# esp32_devkit.net
KiCad netlist of a schematic drawn in Altium Designer
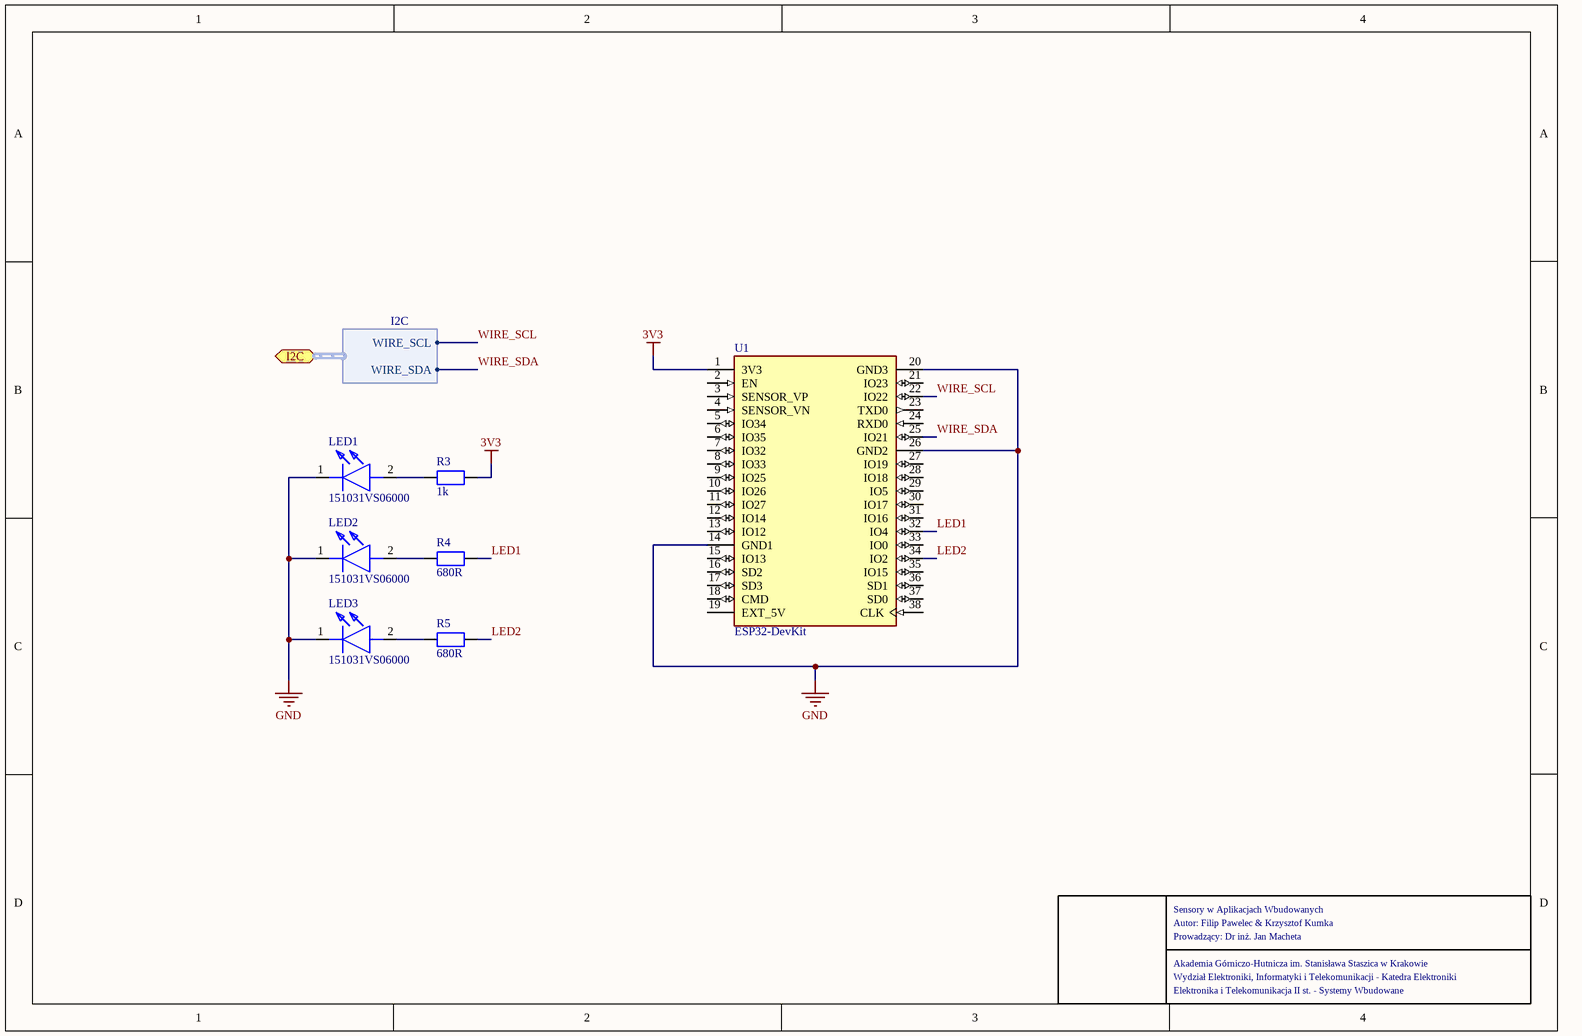
[diagram p0: esp32_devkit.SchDoc]

(export (version "E")
  (design (tool "Eeschema 10.0.6"))
  (components
    (comp (ref "LED1")
      (value "151031VS06000")
      (footprint "TEMD_lib:151034GS03000")
      (description "LED")
      (fields (field (name "MOUSER2 PART NUMBER") "710-151031VS06000"))
      (libsource (lib "*") (part "151031VS06000"))
    )
    (comp (ref "LED2")
      (value "151031VS06000")
      (footprint "TEMD_lib:151034GS03000")
      (description "LED")
      (fields (field (name "MOUSER2 PART NUMBER") "710-151031VS06000"))
      (libsource (lib "TEMD_lib") (part "151031VS06000"))
    )
    (comp (ref "LED3")
      (value "151031VS06000")
      (footprint "TEMD_lib:151034GS03000")
      (description "LED")
      (fields (field (name "MOUSER2 PART NUMBER") "710-151031VS06000"))
      (libsource (lib "TEMD_lib") (part "151031VS06000"))
    )
    (comp (ref "R3")
      (value "1k")
      (footprint "R0603")
      (description "Resistor")
      (libsource (lib "TEMD_lib") (part "R0603"))
    )
    (comp (ref "R4")
      (value "680R")
      (footprint "R0603")
      (description "Resistor")
      (libsource (lib "TEMD_lib") (part "R0603"))
    )
    (comp (ref "R5")
      (value "680R")
      (footprint "R0603")
      (description "Resistor")
      (libsource (lib "TEMD_lib") (part "R0603"))
    )
    (comp (ref "U1")
      (value "ESP32-DevKit")
      (footprint "MODULE_ESP32-DEVKIT")
      (description "ESP32-DevKitC-32UE")
      (libsource (lib "TEMD_lib") (part "ESP32_DEVKIT"))
    )
  )
  (nets
    (net (code "2") (name "/LED1") (class "Default")
      (node (ref "R4") (pin "2") (pinfunction "2_2") (pintype "passive"))
      (node (ref "U1") (pin "32") (pinfunction "IO4_32") (pintype "bidirectional"))
    )
    (net (code "3") (name "/LED2") (class "Default")
      (node (ref "R5") (pin "2") (pinfunction "2_2") (pintype "passive"))
      (node (ref "U1") (pin "34") (pinfunction "IO2_34") (pintype "bidirectional"))
    )
    (net (code "4") (name "/WIRE_SCL") (class "Default")
      (node (ref "U1") (pin "22") (pinfunction "IO22_22") (pintype "bidirectional"))
    )
    (net (code "5") (name "/WIRE_SDA") (class "Default")
      (node (ref "U1") (pin "25") (pinfunction "IO21_25") (pintype "bidirectional"))
    )
    (net (code "7") (name "3V3") (class "Default")
      (node (ref "R3") (pin "2") (pinfunction "2_2") (pintype "passive"))
      (node (ref "U1") (pin "1") (pinfunction "3V3_1") (pintype "power_in"))
    )
    (net (code "8") (name "GND") (class "Default")
      (node (ref "LED1") (pin "1") (pinfunction "K_1") (pintype "passive"))
      (node (ref "LED2") (pin "1") (pinfunction "K_1") (pintype "passive"))
      (node (ref "LED3") (pin "1") (pinfunction "K_1") (pintype "passive"))
      (node (ref "U1") (pin "14") (pinfunction "GND1_14") (pintype "power_in"))
      (node (ref "U1") (pin "20") (pinfunction "GND3_20") (pintype "power_in"))
      (node (ref "U1") (pin "26") (pinfunction "GND2_26") (pintype "power_in"))
    )
    (net (code "9") (name "Net-(LED1-A)") (class "Default")
      (node (ref "LED1") (pin "2") (pinfunction "A_2") (pintype "passive"))
      (node (ref "R3") (pin "1") (pinfunction "1_1") (pintype "passive"))
    )
    (net (code "10") (name "Net-(LED2-A)") (class "Default")
      (node (ref "LED2") (pin "2") (pinfunction "A_2") (pintype "passive"))
      (node (ref "R4") (pin "1") (pinfunction "1_1") (pintype "passive"))
    )
    (net (code "11") (name "Net-(LED3-A)") (class "Default")
      (node (ref "LED3") (pin "2") (pinfunction "A_2") (pintype "passive"))
      (node (ref "R5") (pin "1") (pinfunction "1_1") (pintype "passive"))
    )
    (net (code "12") (name "unconnected-(U1-CLK-Pad38)") (class "Default")
      (node (ref "U1") (pin "38") (pinfunction "CLK_38") (pintype "input"))
    )
    (net (code "13") (name "unconnected-(U1-CMD-Pad18)") (class "Default")
      (node (ref "U1") (pin "18") (pinfunction "CMD_18") (pintype "bidirectional"))
    )
    (net (code "14") (name "unconnected-(U1-EN-Pad2)") (class "Default")
      (node (ref "U1") (pin "2") (pinfunction "EN_2") (pintype "input"))
    )
    (net (code "15") (name "unconnected-(U1-EXT_5V-Pad19)") (class "Default")
      (node (ref "U1") (pin "19") (pinfunction "EXT_5V_19") (pintype "power_in"))
    )
    (net (code "16") (name "unconnected-(U1-IO0-Pad33)") (class "Default")
      (node (ref "U1") (pin "33") (pinfunction "IO0_33") (pintype "bidirectional"))
    )
    (net (code "17") (name "unconnected-(U1-IO5-Pad29)") (class "Default")
      (node (ref "U1") (pin "29") (pinfunction "IO5_29") (pintype "bidirectional"))
    )
    (net (code "18") (name "unconnected-(U1-IO12-Pad13)") (class "Default")
      (node (ref "U1") (pin "13") (pinfunction "IO12_13") (pintype "bidirectional"))
    )
    (net (code "19") (name "unconnected-(U1-IO13-Pad15)") (class "Default")
      (node (ref "U1") (pin "15") (pinfunction "IO13_15") (pintype "bidirectional"))
    )
    (net (code "20") (name "unconnected-(U1-IO14-Pad12)") (class "Default")
      (node (ref "U1") (pin "12") (pinfunction "IO14_12") (pintype "bidirectional"))
    )
    (net (code "21") (name "unconnected-(U1-IO15-Pad35)") (class "Default")
      (node (ref "U1") (pin "35") (pinfunction "IO15_35") (pintype "bidirectional"))
    )
    (net (code "22") (name "unconnected-(U1-IO16-Pad31)") (class "Default")
      (node (ref "U1") (pin "31") (pinfunction "IO16_31") (pintype "bidirectional"))
    )
    (net (code "23") (name "unconnected-(U1-IO17-Pad30)") (class "Default")
      (node (ref "U1") (pin "30") (pinfunction "IO17_30") (pintype "bidirectional"))
    )
    (net (code "24") (name "unconnected-(U1-IO18-Pad28)") (class "Default")
      (node (ref "U1") (pin "28") (pinfunction "IO18_28") (pintype "bidirectional"))
    )
    (net (code "25") (name "unconnected-(U1-IO19-Pad27)") (class "Default")
      (node (ref "U1") (pin "27") (pinfunction "IO19_27") (pintype "bidirectional"))
    )
    (net (code "26") (name "unconnected-(U1-IO23-Pad21)") (class "Default")
      (node (ref "U1") (pin "21") (pinfunction "IO23_21") (pintype "bidirectional"))
    )
    (net (code "27") (name "unconnected-(U1-IO25-Pad9)") (class "Default")
      (node (ref "U1") (pin "9") (pinfunction "IO25_9") (pintype "bidirectional"))
    )
    (net (code "28") (name "unconnected-(U1-IO26-Pad10)") (class "Default")
      (node (ref "U1") (pin "10") (pinfunction "IO26_10") (pintype "bidirectional"))
    )
    (net (code "29") (name "unconnected-(U1-IO27-Pad11)") (class "Default")
      (node (ref "U1") (pin "11") (pinfunction "IO27_11") (pintype "bidirectional"))
    )
    (net (code "30") (name "unconnected-(U1-IO32-Pad7)") (class "Default")
      (node (ref "U1") (pin "7") (pinfunction "IO32_7") (pintype "bidirectional"))
    )
    (net (code "31") (name "unconnected-(U1-IO33-Pad8)") (class "Default")
      (node (ref "U1") (pin "8") (pinfunction "IO33_8") (pintype "bidirectional"))
    )
    (net (code "32") (name "unconnected-(U1-IO34-Pad5)") (class "Default")
      (node (ref "U1") (pin "5") (pinfunction "IO34_5") (pintype "bidirectional"))
    )
    (net (code "33") (name "unconnected-(U1-IO35-Pad6)") (class "Default")
      (node (ref "U1") (pin "6") (pinfunction "IO35_6") (pintype "bidirectional"))
    )
    (net (code "34") (name "unconnected-(U1-RXD0-Pad24)") (class "Default")
      (node (ref "U1") (pin "24") (pinfunction "RXD0_24") (pintype "input"))
    )
    (net (code "35") (name "unconnected-(U1-SD0-Pad37)") (class "Default")
      (node (ref "U1") (pin "37") (pinfunction "SD0_37") (pintype "bidirectional"))
    )
    (net (code "36") (name "unconnected-(U1-SD1-Pad36)") (class "Default")
      (node (ref "U1") (pin "36") (pinfunction "SD1_36") (pintype "bidirectional"))
    )
    (net (code "37") (name "unconnected-(U1-SD2-Pad16)") (class "Default")
      (node (ref "U1") (pin "16") (pinfunction "SD2_16") (pintype "bidirectional"))
    )
    (net (code "38") (name "unconnected-(U1-SD3-Pad17)") (class "Default")
      (node (ref "U1") (pin "17") (pinfunction "SD3_17") (pintype "bidirectional"))
    )
    (net (code "39") (name "unconnected-(U1-SENSOR_VN-Pad4)") (class "Default")
      (node (ref "U1") (pin "4") (pinfunction "SENSOR_VN_4") (pintype "input"))
    )
    (net (code "40") (name "unconnected-(U1-SENSOR_VP-Pad3)") (class "Default")
      (node (ref "U1") (pin "3") (pinfunction "SENSOR_VP_3") (pintype "input"))
    )
    (net (code "41") (name "unconnected-(U1-TXD0-Pad23)") (class "Default")
      (node (ref "U1") (pin "23") (pinfunction "TXD0_23") (pintype "output"))
    )
  )
)
